# FrontSense.net
KiCad netlist of a schematic drawn in Altium Designer
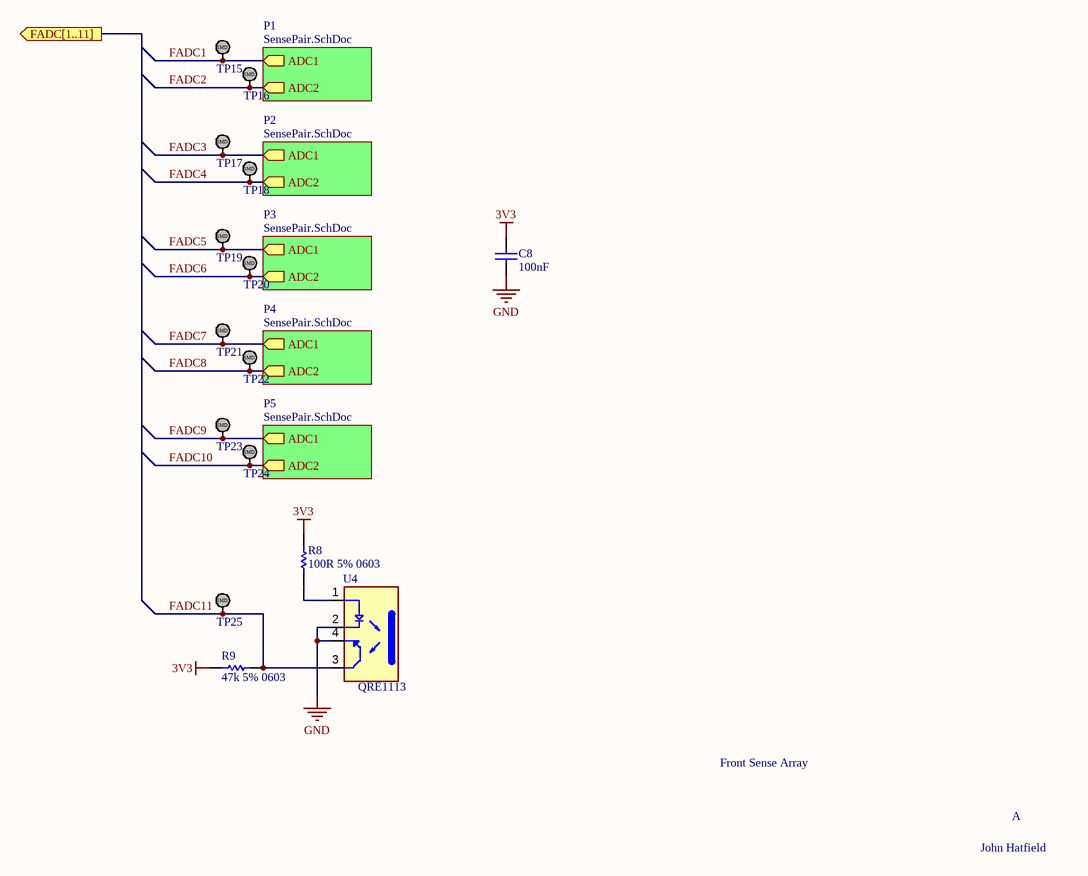
[diagram p0: FrontSense.SchDoc]

(export (version "E")
  (design (tool "Eeschema 10.0.6"))
  (components
    (comp (ref "C8")
      (value "100nF")
      (footprint "Cap_Ceramic_0603")
      (description "Capacitor, Ceramic, SMD, 100nF, 50V, 5%, X7R, 0603")
      (libsource (lib "StandardCapacitors") (part "100nF 50V 5% X7R 0603"))
    )
    (comp (ref "R8")
      (value "100R 5% 0603")
      (footprint "Res_ThinFilm_0603")
      (description "Resistor, SMD, 100R, 0.1W, 5%, 0603")
      (libsource (lib "StandardResistors") (part "100R 5%, 0603"))
    )
    (comp (ref "R9")
      (value "47k 5% 0603")
      (footprint "Res_ThinFilm_0603")
      (description "Resistor, SMD, 47k, 0.1W, 5%, 0603")
      (libsource (lib "StandardResistors") (part "47k 5% 0603"))
    )
    (comp (ref "TP15")
      (value "TestPoint_SMD")
      (footprint "TestPointSMD")
      (libsource (lib "StandardTest") (part "TestPoint_SMD"))
    )
    (comp (ref "TP16")
      (value "TestPoint_SMD")
      (footprint "TestPointSMD")
      (libsource (lib "StandardTest") (part "TestPoint_SMD"))
    )
    (comp (ref "TP17")
      (value "TestPoint_SMD")
      (footprint "TestPointSMD")
      (libsource (lib "StandardTest") (part "TestPoint_SMD"))
    )
    (comp (ref "TP18")
      (value "TestPoint_SMD")
      (footprint "TestPointSMD")
      (libsource (lib "StandardTest") (part "TestPoint_SMD"))
    )
    (comp (ref "TP19")
      (value "TestPoint_SMD")
      (footprint "TestPointSMD")
      (libsource (lib "StandardTest") (part "TestPoint_SMD"))
    )
    (comp (ref "TP20")
      (value "TestPoint_SMD")
      (footprint "TestPointSMD")
      (libsource (lib "StandardTest") (part "TestPoint_SMD"))
    )
    (comp (ref "TP21")
      (value "TestPoint_SMD")
      (footprint "TestPointSMD")
      (libsource (lib "StandardTest") (part "TestPoint_SMD"))
    )
    (comp (ref "TP22")
      (value "TestPoint_SMD")
      (footprint "TestPointSMD")
      (libsource (lib "StandardTest") (part "TestPoint_SMD"))
    )
    (comp (ref "TP23")
      (value "TestPoint_SMD")
      (footprint "TestPointSMD")
      (libsource (lib "StandardTest") (part "TestPoint_SMD"))
    )
    (comp (ref "TP24")
      (value "TestPoint_SMD")
      (footprint "TestPointSMD")
      (libsource (lib "StandardTest") (part "TestPoint_SMD"))
    )
    (comp (ref "TP25")
      (value "TestPoint_SMD")
      (footprint "TestPointSMD")
      (libsource (lib "StandardTest") (part "TestPoint_SMD"))
    )
    (comp (ref "U4")
      (value "QRE1113")
      (footprint "DIP400W50P180L360H200Q4")
      (description "Reflective Optical Sensor 0.197 _5mm_ 4-DIP _0.157, 4.00mm_")
      (fields (field (name "MF") "ON Semiconductor"))
      (libsource (lib "QRE1113") (part "QRE1113"))
    )
  )
  (nets
    (net (code "1") (name "/FADC1") (class "Default")
      (node (ref "TP15") (pin "1") (pinfunction "1_1") (pintype "passive"))
    )
    (net (code "2") (name "/FADC2") (class "Default")
      (node (ref "TP16") (pin "1") (pinfunction "1_1") (pintype "passive"))
    )
    (net (code "3") (name "/FADC3") (class "Default")
      (node (ref "TP17") (pin "1") (pinfunction "1_1") (pintype "passive"))
    )
    (net (code "4") (name "/FADC4") (class "Default")
      (node (ref "TP18") (pin "1") (pinfunction "1_1") (pintype "passive"))
    )
    (net (code "5") (name "/FADC5") (class "Default")
      (node (ref "TP19") (pin "1") (pinfunction "1_1") (pintype "passive"))
    )
    (net (code "6") (name "/FADC6") (class "Default")
      (node (ref "TP20") (pin "1") (pinfunction "1_1") (pintype "passive"))
    )
    (net (code "7") (name "/FADC7") (class "Default")
      (node (ref "TP21") (pin "1") (pinfunction "1_1") (pintype "passive"))
    )
    (net (code "8") (name "/FADC8") (class "Default")
      (node (ref "TP22") (pin "1") (pinfunction "1_1") (pintype "passive"))
    )
    (net (code "9") (name "/FADC9") (class "Default")
      (node (ref "TP23") (pin "1") (pinfunction "1_1") (pintype "passive"))
    )
    (net (code "10") (name "/FADC10") (class "Default")
      (node (ref "TP24") (pin "1") (pinfunction "1_1") (pintype "passive"))
    )
    (net (code "11") (name "/FADC11") (class "Default")
      (node (ref "R9") (pin "2") (pinfunction "2_2") (pintype "passive"))
      (node (ref "TP25") (pin "1") (pinfunction "1_1") (pintype "passive"))
      (node (ref "U4") (pin "3") (pinfunction "CT_3") (pintype "passive"))
    )
    (net (code "13") (name "3V3") (class "Default")
      (node (ref "C8") (pin "2") (pinfunction "2_2") (pintype "passive"))
      (node (ref "R8") (pin "2") (pinfunction "2_2") (pintype "passive"))
      (node (ref "R9") (pin "1") (pinfunction "1_1") (pintype "passive"))
    )
    (net (code "14") (name "GND") (class "Default")
      (node (ref "C8") (pin "1") (pinfunction "1_1") (pintype "passive"))
      (node (ref "U4") (pin "2") (pinfunction "C_2") (pintype "passive"))
      (node (ref "U4") (pin "4") (pinfunction "ET_4") (pintype "passive"))
    )
    (net (code "15") (name "Net-(U4-A)") (class "Default")
      (node (ref "R8") (pin "1") (pinfunction "1_1") (pintype "passive"))
      (node (ref "U4") (pin "1") (pinfunction "A_1") (pintype "passive"))
    )
  )
)
